# ControlID.net
KiCad netlist of a schematic drawn in EAGLE
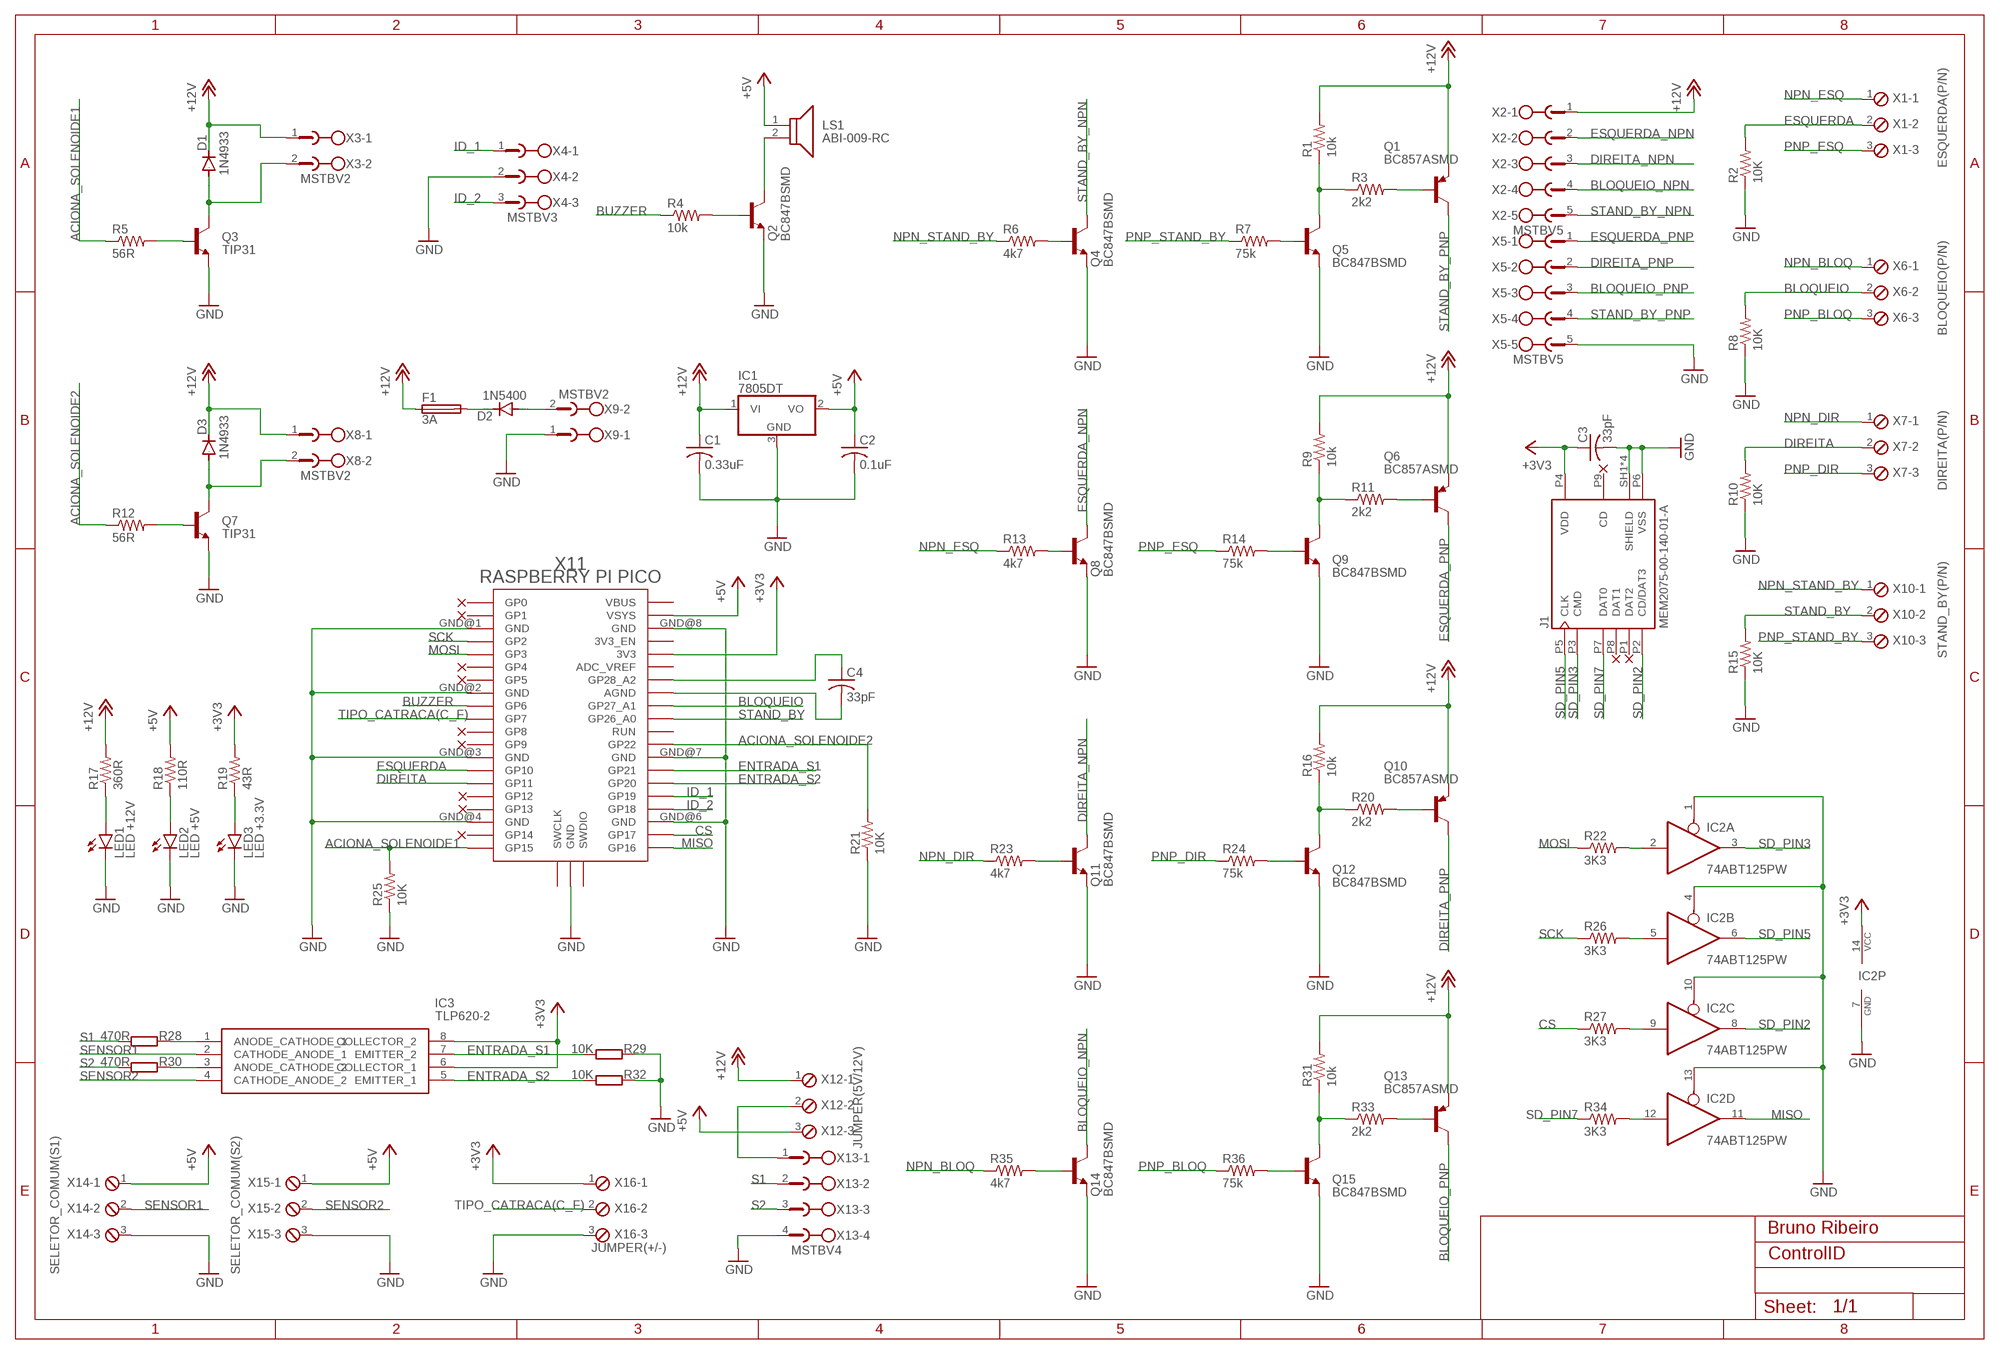
[diagram p0: schematic, sheet 1]

(export (version "E")
  (design (tool "Eeschema 10.0.6"))
  (components
    (comp (ref "C1")
      (value "0.33uF")
      (footprint "eagle-import:C0805")
      (libsource (lib "eagle-import") (part "C-USC0805"))
    )
    (comp (ref "C2")
      (value "0.1uF")
      (footprint "eagle-import:C0805")
      (libsource (lib "eagle-import") (part "C-USC0805"))
    )
    (comp (ref "C3")
      (value "33pF")
      (footprint "eagle-import:C0805")
      (libsource (lib "eagle-import") (part "C-USC0805"))
    )
    (comp (ref "C4")
      (value "33pF")
      (footprint "eagle-import:C0805")
      (libsource (lib "eagle-import") (part "C-USC0805"))
    )
    (comp (ref "D1")
      (value "1N4933")
      (footprint "eagle-import:DO41-10")
      (libsource (lib "eagle-import") (part "1N4933"))
    )
    (comp (ref "D2")
      (value "1N5400")
      (footprint "eagle-import:DO201-15")
      (libsource (lib "eagle-import") (part "1N5400"))
    )
    (comp (ref "D3")
      (value "1N4933")
      (footprint "eagle-import:DO41-10")
      (libsource (lib "eagle-import") (part "1N4933"))
    )
    (comp (ref "F1")
      (value "3A")
      (footprint "eagle-import:SH22,5A")
      (fields (field (name "MPN") "0031.7701.11"))
      (libsource (lib "eagle-import") (part "SH22,5A"))
    )
    (comp (ref "IC1")
      (value "7805DT")
      (footprint "eagle-import:TO252")
      (libsource (lib "eagle-import") (part "78DT05"))
    )
    (comp (ref "IC2")
      (value "74ABT125PW")
      (footprint "eagle-import:TSSOP14")
      (libsource (lib "eagle-import") (part "74125PWABT"))
    )
    (comp (ref "IC3")
      (value "TLP620-2")
      (footprint "eagle-import:DIP762W60P254L966H485Q8N")
      (libsource (lib "eagle-import") (part "TLP620-2"))
    )
    (comp (ref "J1")
      (value "MEM2075-00-140-01-A")
      (footprint "eagle-import:GCT_MEM2075-00-140-01-A")
      (fields (field (name "MF") "Global Connector Technology"))
      (libsource (lib "eagle-import") (part "MEM2075-00-140-01-A"))
    )
    (comp (ref "LED1")
      (value "LED +12V")
      (footprint "eagle-import:CHIP-LED0805")
      (libsource (lib "eagle-import") (part "LEDCHIP-LED0805"))
    )
    (comp (ref "LED2")
      (value "LED +5V")
      (footprint "eagle-import:CHIP-LED0805")
      (libsource (lib "eagle-import") (part "LEDCHIP-LED0805"))
    )
    (comp (ref "LED3")
      (value "LED +3.3V")
      (footprint "eagle-import:CHIP-LED0805")
      (libsource (lib "eagle-import") (part "LEDCHIP-LED0805"))
    )
    (comp (ref "LS1")
      (value "ABI-009-RC")
      (footprint "eagle-import:ABI-009-RC")
      (libsource (lib "eagle-import") (part "ABI-009-RC"))
    )
    (comp (ref "Q1")
      (value "BC857ASMD")
      (footprint "eagle-import:SOT23-BEC")
      (libsource (lib "eagle-import") (part "BC857SMDA"))
    )
    (comp (ref "Q2")
      (value "BC847BSMD")
      (footprint "eagle-import:SOT23")
      (libsource (lib "eagle-import") (part "BC847SMDB"))
    )
    (comp (ref "Q3")
      (value "TIP31")
      (footprint "eagle-import:TO254P1060X482X2222-3")
      (fields (field (name "MF") "ON Semiconductor"))
      (libsource (lib "eagle-import") (part "TIP31"))
    )
    (comp (ref "Q4")
      (value "BC847BSMD")
      (footprint "eagle-import:SOT23")
      (libsource (lib "eagle-import") (part "BC847SMDB"))
    )
    (comp (ref "Q5")
      (value "BC847BSMD")
      (footprint "eagle-import:SOT23")
      (libsource (lib "eagle-import") (part "BC847SMDB"))
    )
    (comp (ref "Q6")
      (value "BC857ASMD")
      (footprint "eagle-import:SOT23-BEC")
      (libsource (lib "eagle-import") (part "BC857SMDA"))
    )
    (comp (ref "Q7")
      (value "TIP31")
      (footprint "eagle-import:TO254P1060X482X2222-3")
      (fields (field (name "MF") "ON Semiconductor"))
      (libsource (lib "eagle-import") (part "TIP31"))
    )
    (comp (ref "Q8")
      (value "BC847BSMD")
      (footprint "eagle-import:SOT23")
      (libsource (lib "eagle-import") (part "BC847SMDB"))
    )
    (comp (ref "Q9")
      (value "BC847BSMD")
      (footprint "eagle-import:SOT23")
      (libsource (lib "eagle-import") (part "BC847SMDB"))
    )
    (comp (ref "Q10")
      (value "BC857ASMD")
      (footprint "eagle-import:SOT23-BEC")
      (libsource (lib "eagle-import") (part "BC857SMDA"))
    )
    (comp (ref "Q11")
      (value "BC847BSMD")
      (footprint "eagle-import:SOT23")
      (libsource (lib "eagle-import") (part "BC847SMDB"))
    )
    (comp (ref "Q12")
      (value "BC847BSMD")
      (footprint "eagle-import:SOT23")
      (libsource (lib "eagle-import") (part "BC847SMDB"))
    )
    (comp (ref "Q13")
      (value "BC857ASMD")
      (footprint "eagle-import:SOT23-BEC")
      (libsource (lib "eagle-import") (part "BC857SMDA"))
    )
    (comp (ref "Q14")
      (value "BC847BSMD")
      (footprint "eagle-import:SOT23")
      (libsource (lib "eagle-import") (part "BC847SMDB"))
    )
    (comp (ref "Q15")
      (value "BC847BSMD")
      (footprint "eagle-import:SOT23")
      (libsource (lib "eagle-import") (part "BC847SMDB"))
    )
    (comp (ref "R1")
      (value "10k")
      (footprint "eagle-import:R0805")
      (libsource (lib "eagle-import") (part "R-US_R0805"))
    )
    (comp (ref "R2")
      (value "10K")
      (footprint "eagle-import:R0805")
      (libsource (lib "eagle-import") (part "R-US_R0805"))
    )
    (comp (ref "R3")
      (value "2k2")
      (footprint "eagle-import:R0805")
      (libsource (lib "eagle-import") (part "R-US_R0805"))
    )
    (comp (ref "R4")
      (value "10k")
      (footprint "eagle-import:R0805")
      (libsource (lib "eagle-import") (part "R-US_R0805"))
    )
    (comp (ref "R5")
      (value "56R")
      (footprint "eagle-import:R0805")
      (libsource (lib "eagle-import") (part "R-US_R0805"))
    )
    (comp (ref "R6")
      (value "4k7")
      (footprint "eagle-import:R0805")
      (libsource (lib "eagle-import") (part "R-US_R0805"))
    )
    (comp (ref "R7")
      (value "75k")
      (footprint "eagle-import:R0805")
      (libsource (lib "eagle-import") (part "R-US_R0805"))
    )
    (comp (ref "R8")
      (value "10K")
      (footprint "eagle-import:R0805")
      (libsource (lib "eagle-import") (part "R-US_R0805"))
    )
    (comp (ref "R9")
      (value "10k")
      (footprint "eagle-import:R0805")
      (libsource (lib "eagle-import") (part "R-US_R0805"))
    )
    (comp (ref "R10")
      (value "10K")
      (footprint "eagle-import:R0805")
      (libsource (lib "eagle-import") (part "R-US_R0805"))
    )
    (comp (ref "R11")
      (value "2k2")
      (footprint "eagle-import:R0805")
      (libsource (lib "eagle-import") (part "R-US_R0805"))
    )
    (comp (ref "R12")
      (value "56R")
      (footprint "eagle-import:R0805")
      (libsource (lib "eagle-import") (part "R-US_R0805"))
    )
    (comp (ref "R13")
      (value "4k7")
      (footprint "eagle-import:R0805")
      (libsource (lib "eagle-import") (part "R-US_R0805"))
    )
    (comp (ref "R14")
      (value "75k")
      (footprint "eagle-import:R0805")
      (libsource (lib "eagle-import") (part "R-US_R0805"))
    )
    (comp (ref "R15")
      (value "10K")
      (footprint "eagle-import:R0805")
      (libsource (lib "eagle-import") (part "R-US_R0805"))
    )
    (comp (ref "R16")
      (value "10k")
      (footprint "eagle-import:R0805")
      (libsource (lib "eagle-import") (part "R-US_R0805"))
    )
    (comp (ref "R17")
      (value "360R")
      (footprint "eagle-import:R0805")
      (libsource (lib "eagle-import") (part "R-US_R0805"))
    )
    (comp (ref "R18")
      (value "110R")
      (footprint "eagle-import:R0805")
      (libsource (lib "eagle-import") (part "R-US_R0805"))
    )
    (comp (ref "R19")
      (value "43R")
      (footprint "eagle-import:R0805")
      (libsource (lib "eagle-import") (part "R-US_R0805"))
    )
    (comp (ref "R20")
      (value "2k2")
      (footprint "eagle-import:R0805")
      (libsource (lib "eagle-import") (part "R-US_R0805"))
    )
    (comp (ref "R21")
      (value "10K")
      (footprint "eagle-import:R0805")
      (libsource (lib "eagle-import") (part "R-US_R0805"))
    )
    (comp (ref "R22")
      (value "3K3")
      (footprint "eagle-import:R0805")
      (libsource (lib "eagle-import") (part "R-US_R0805"))
    )
    (comp (ref "R23")
      (value "4k7")
      (footprint "eagle-import:R0805")
      (libsource (lib "eagle-import") (part "R-US_R0805"))
    )
    (comp (ref "R24")
      (value "75k")
      (footprint "eagle-import:R0805")
      (libsource (lib "eagle-import") (part "R-US_R0805"))
    )
    (comp (ref "R25")
      (value "10K")
      (footprint "eagle-import:R0805")
      (libsource (lib "eagle-import") (part "R-US_R0805"))
    )
    (comp (ref "R26")
      (value "3K3")
      (footprint "eagle-import:R0805")
      (libsource (lib "eagle-import") (part "R-US_R0805"))
    )
    (comp (ref "R27")
      (value "3K3")
      (footprint "eagle-import:R0805")
      (libsource (lib "eagle-import") (part "R-US_R0805"))
    )
    (comp (ref "R28")
      (value "470R")
      (footprint "eagle-import:R0805")
      (libsource (lib "eagle-import") (part "R-EU_R0805"))
    )
    (comp (ref "R29")
      (value "10K")
      (footprint "eagle-import:R0805")
      (libsource (lib "eagle-import") (part "R-EU_R0805"))
    )
    (comp (ref "R30")
      (value "470R")
      (footprint "eagle-import:R0805")
      (libsource (lib "eagle-import") (part "R-EU_R0805"))
    )
    (comp (ref "R31")
      (value "10k")
      (footprint "eagle-import:R0805")
      (libsource (lib "eagle-import") (part "R-US_R0805"))
    )
    (comp (ref "R32")
      (value "10K")
      (footprint "eagle-import:R0805")
      (libsource (lib "eagle-import") (part "R-EU_R0805"))
    )
    (comp (ref "R33")
      (value "2k2")
      (footprint "eagle-import:R0805")
      (libsource (lib "eagle-import") (part "R-US_R0805"))
    )
    (comp (ref "R34")
      (value "3K3")
      (footprint "eagle-import:R0805")
      (libsource (lib "eagle-import") (part "R-US_R0805"))
    )
    (comp (ref "R35")
      (value "4k7")
      (footprint "eagle-import:R0805")
      (libsource (lib "eagle-import") (part "R-US_R0805"))
    )
    (comp (ref "R36")
      (value "75k")
      (footprint "eagle-import:R0805")
      (libsource (lib "eagle-import") (part "R-US_R0805"))
    )
    (comp (ref "X1")
      (value "ESQUERDA(P/N)")
      (footprint "eagle-import:3POL254")
      (libsource (lib "eagle-import") (part "MPT3"))
    )
    (comp (ref "X2")
      (value "MSTBV5")
      (footprint "eagle-import:MSTBV5")
      (fields (field (name "MPN") "MSTBV 2,5/5-GF-5.08"))
      (libsource (lib "eagle-import") (part "MSTBV5"))
    )
    (comp (ref "X3")
      (value "MSTBV2")
      (footprint "eagle-import:MSTBV2")
      (fields (field (name "MPN") "MSTBV 2,5/2-GF-5.08"))
      (libsource (lib "eagle-import") (part "MSTBV2"))
    )
    (comp (ref "X4")
      (value "MSTBV3")
      (footprint "eagle-import:MSTBV3")
      (fields (field (name "MPN") "MSTBV 2,5/3-GF-5.08"))
      (libsource (lib "eagle-import") (part "MSTBV3"))
    )
    (comp (ref "X5")
      (value "MSTBV5")
      (footprint "eagle-import:MSTBV5")
      (fields (field (name "MPN") "MSTBV 2,5/5-GF-5.08"))
      (libsource (lib "eagle-import") (part "MSTBV5"))
    )
    (comp (ref "X6")
      (value "BLOQUEIO(P/N)")
      (footprint "eagle-import:3POL254")
      (libsource (lib "eagle-import") (part "MPT3"))
    )
    (comp (ref "X7")
      (value "DIREITA(P/N)")
      (footprint "eagle-import:3POL254")
      (libsource (lib "eagle-import") (part "MPT3"))
    )
    (comp (ref "X8")
      (value "MSTBV2")
      (footprint "eagle-import:MSTBV2")
      (fields (field (name "MPN") "MSTBV 2,5/2-GF-5.08"))
      (libsource (lib "eagle-import") (part "MSTBV2"))
    )
    (comp (ref "X9")
      (value "MSTBV2")
      (footprint "eagle-import:MSTBV2")
      (fields (field (name "MPN") "MSTBV 2,5/2-GF-5.08"))
      (libsource (lib "eagle-import") (part "MSTBV2"))
    )
    (comp (ref "X10")
      (value "STAND_BY(P/N)")
      (footprint "eagle-import:3POL254")
      (libsource (lib "eagle-import") (part "MPT3"))
    )
    (comp (ref "X11")
      (value "RASPBERRY PI PICO")
      (footprint "eagle-import:RPI_PICO_TH")
      (libsource (lib "eagle-import") (part "RPI_PICO_IG-TH"))
    )
    (comp (ref "X12")
      (value "JUMPER(5V/12V)")
      (footprint "eagle-import:3POL254")
      (libsource (lib "eagle-import") (part "MPT3"))
    )
    (comp (ref "X13")
      (value "MSTBV4")
      (footprint "eagle-import:MSTBV4")
      (fields (field (name "MPN") "MSTBV 2,5/4-GF-5.08"))
      (libsource (lib "eagle-import") (part "MSTBV4"))
    )
    (comp (ref "X14")
      (value "SELETOR_COMUM(S1)")
      (footprint "eagle-import:3POL254")
      (libsource (lib "eagle-import") (part "MPT3"))
    )
    (comp (ref "X15")
      (value "SELETOR_COMUM(S2)")
      (footprint "eagle-import:3POL254")
      (libsource (lib "eagle-import") (part "MPT3"))
    )
    (comp (ref "X16")
      (value "JUMPER(+/-)")
      (footprint "eagle-import:3POL254")
      (libsource (lib "eagle-import") (part "MPT3"))
    )
  )
  (nets
    (net (code "1") (name "+3V3") (class "Default")
      (node (ref "C3") (pin "1") (pinfunction "1_1") (pintype "passive"))
      (node (ref "IC2") (pin "14") (pinfunction "VCC_14") (pintype "power_in"))
      (node (ref "IC3") (pin "6") (pinfunction "COLLECTOR_1_6") (pintype "bidirectional"))
      (node (ref "IC3") (pin "8") (pinfunction "COLLECTOR_2_8") (pintype "bidirectional"))
      (node (ref "J1") (pin "P4") (pinfunction "VDD_P4") (pintype "power_in"))
      (node (ref "R19") (pin "2") (pinfunction "2_2") (pintype "passive"))
      (node (ref "X11") (pin "3V3") (pinfunction "3V3_3V3") (pintype "bidirectional"))
      (node (ref "X16") (pin "1") (pinfunction "1_1") (pintype "passive"))
    )
    (net (code "2") (name "+5V") (class "Default")
      (node (ref "C2") (pin "1") (pinfunction "1_1") (pintype "passive"))
      (node (ref "IC1") (pin "2") (pinfunction "VO_2") (pintype "passive"))
      (node (ref "LS1") (pin "1") (pinfunction "1_1") (pintype "bidirectional"))
      (node (ref "R18") (pin "2") (pinfunction "2_2") (pintype "passive"))
      (node (ref "X11") (pin "VSYS") (pinfunction "VSYS_VSYS") (pintype "bidirectional"))
      (node (ref "X12") (pin "3") (pinfunction "1_3") (pintype "passive"))
      (node (ref "X14") (pin "1") (pinfunction "1_1") (pintype "passive"))
      (node (ref "X15") (pin "1") (pinfunction "1_1") (pintype "passive"))
    )
    (net (code "3") (name "+12V") (class "Default")
      (node (ref "C1") (pin "1") (pinfunction "1_1") (pintype "passive"))
      (node (ref "D1") (pin "C") (pinfunction "C_C") (pintype "passive"))
      (node (ref "D3") (pin "C") (pinfunction "C_C") (pintype "passive"))
      (node (ref "F1") (pin "1") (pinfunction "1_1") (pintype "passive"))
      (node (ref "IC1") (pin "1") (pinfunction "VI_1") (pintype "input"))
      (node (ref "Q1") (pin "E") (pinfunction "E_E") (pintype "passive"))
      (node (ref "Q10") (pin "E") (pinfunction "E_E") (pintype "passive"))
      (node (ref "Q13") (pin "E") (pinfunction "E_E") (pintype "passive"))
      (node (ref "Q6") (pin "E") (pinfunction "E_E") (pintype "passive"))
      (node (ref "R1") (pin "2") (pinfunction "2_2") (pintype "passive"))
      (node (ref "R16") (pin "2") (pinfunction "2_2") (pintype "passive"))
      (node (ref "R17") (pin "2") (pinfunction "2_2") (pintype "passive"))
      (node (ref "R31") (pin "2") (pinfunction "2_2") (pintype "passive"))
      (node (ref "R9") (pin "2") (pinfunction "2_2") (pintype "passive"))
      (node (ref "X12") (pin "1") (pinfunction "1_1") (pintype "passive"))
      (node (ref "X2") (pin "1") (pinfunction "1_1") (pintype "passive"))
      (node (ref "X3") (pin "1") (pinfunction "1_1") (pintype "passive"))
      (node (ref "X8") (pin "1") (pinfunction "1_1") (pintype "passive"))
    )
    (net (code "4") (name "/ACIONA_SOLENOIDE1") (class "Default")
      (node (ref "R25") (pin "2") (pinfunction "2_2") (pintype "passive"))
      (node (ref "R5") (pin "1") (pinfunction "1_1") (pintype "passive"))
      (node (ref "X11") (pin "GP15") (pinfunction "GP15_GP15") (pintype "bidirectional"))
    )
    (net (code "5") (name "/ACIONA_SOLENOIDE2") (class "Default")
      (node (ref "R12") (pin "1") (pinfunction "1_1") (pintype "passive"))
      (node (ref "R21") (pin "2") (pinfunction "2_2") (pintype "passive"))
      (node (ref "X11") (pin "GP22") (pinfunction "GP22_GP22") (pintype "bidirectional"))
    )
    (net (code "6") (name "/BLOQUEIO") (class "Default")
      (node (ref "R8") (pin "2") (pinfunction "2_2") (pintype "passive"))
      (node (ref "X11") (pin "GP27_A1") (pinfunction "GP27_A1_GP27_A1") (pintype "bidirectional"))
      (node (ref "X6") (pin "2") (pinfunction "1_2") (pintype "passive"))
    )
    (net (code "7") (name "/BLOQUEIO_NPN") (class "Default")
      (node (ref "Q14") (pin "3") (pinfunction "C_3") (pintype "passive"))
      (node (ref "X2") (pin "4") (pinfunction "1_4") (pintype "passive"))
    )
    (net (code "8") (name "/BLOQUEIO_PNP") (class "Default")
      (node (ref "Q13") (pin "C") (pinfunction "C_C") (pintype "passive"))
      (node (ref "X5") (pin "3") (pinfunction "1_3") (pintype "passive"))
    )
    (net (code "9") (name "/BUZZER") (class "Default")
      (node (ref "R4") (pin "1") (pinfunction "1_1") (pintype "passive"))
      (node (ref "X11") (pin "GP6") (pinfunction "GP6_GP6") (pintype "bidirectional"))
    )
    (net (code "10") (name "/CS") (class "Default")
      (node (ref "R27") (pin "1") (pinfunction "1_1") (pintype "passive"))
      (node (ref "X11") (pin "GP17") (pinfunction "GP17_GP17") (pintype "bidirectional"))
    )
    (net (code "11") (name "/DIREITA") (class "Default")
      (node (ref "R10") (pin "2") (pinfunction "2_2") (pintype "passive"))
      (node (ref "X11") (pin "GP11") (pinfunction "GP11_GP11") (pintype "bidirectional"))
      (node (ref "X7") (pin "2") (pinfunction "1_2") (pintype "passive"))
    )
    (net (code "12") (name "/DIREITA_NPN") (class "Default")
      (node (ref "Q11") (pin "3") (pinfunction "C_3") (pintype "passive"))
      (node (ref "X2") (pin "3") (pinfunction "1_3") (pintype "passive"))
    )
    (net (code "13") (name "/DIREITA_PNP") (class "Default")
      (node (ref "Q10") (pin "C") (pinfunction "C_C") (pintype "passive"))
      (node (ref "X5") (pin "2") (pinfunction "1_2") (pintype "passive"))
    )
    (net (code "14") (name "/ENTRADA_S1") (class "Default")
      (node (ref "IC3") (pin "7") (pinfunction "EMITTER_2_7") (pintype "bidirectional"))
      (node (ref "R29") (pin "2") (pinfunction "2_2") (pintype "passive"))
      (node (ref "X11") (pin "GP21") (pinfunction "GP21_GP21") (pintype "bidirectional"))
    )
    (net (code "15") (name "/ENTRADA_S2") (class "Default")
      (node (ref "IC3") (pin "5") (pinfunction "EMITTER_1_5") (pintype "bidirectional"))
      (node (ref "R32") (pin "2") (pinfunction "2_2") (pintype "passive"))
      (node (ref "X11") (pin "GP20") (pinfunction "GP20_GP20") (pintype "bidirectional"))
    )
    (net (code "16") (name "/ESQUERDA") (class "Default")
      (node (ref "R2") (pin "2") (pinfunction "2_2") (pintype "passive"))
      (node (ref "X1") (pin "2") (pinfunction "1_2") (pintype "passive"))
      (node (ref "X11") (pin "GP10") (pinfunction "GP10_GP10") (pintype "bidirectional"))
    )
    (net (code "17") (name "/ESQUERDA_NPN") (class "Default")
      (node (ref "Q8") (pin "3") (pinfunction "C_3") (pintype "passive"))
      (node (ref "X2") (pin "2") (pinfunction "1_2") (pintype "passive"))
    )
    (net (code "18") (name "/ESQUERDA_PNP") (class "Default")
      (node (ref "Q6") (pin "C") (pinfunction "C_C") (pintype "passive"))
      (node (ref "X5") (pin "1") (pinfunction "1_1") (pintype "passive"))
    )
    (net (code "19") (name "/ID_1") (class "Default")
      (node (ref "X11") (pin "GP19") (pinfunction "GP19_GP19") (pintype "bidirectional"))
      (node (ref "X4") (pin "1") (pinfunction "1_1") (pintype "passive"))
    )
    (net (code "20") (name "/ID_2") (class "Default")
      (node (ref "X11") (pin "GP18") (pinfunction "GP18_GP18") (pintype "bidirectional"))
      (node (ref "X4") (pin "3") (pinfunction "1_3") (pintype "passive"))
    )
    (net (code "21") (name "/MISO") (class "Default")
      (node (ref "IC2") (pin "11") (pinfunction "O_11") (pintype "tri_state"))
      (node (ref "X11") (pin "GP16") (pinfunction "GP16_GP16") (pintype "bidirectional"))
    )
    (net (code "22") (name "/MOSI") (class "Default")
      (node (ref "R22") (pin "1") (pinfunction "1_1") (pintype "passive"))
      (node (ref "X11") (pin "GP3") (pinfunction "GP3_GP3") (pintype "bidirectional"))
    )
    (net (code "23") (name "/NPN_BLOQ") (class "Default")
      (node (ref "R35") (pin "1") (pinfunction "1_1") (pintype "passive"))
      (node (ref "X6") (pin "1") (pinfunction "1_1") (pintype "passive"))
    )
    (net (code "24") (name "/NPN_DIR") (class "Default")
      (node (ref "R23") (pin "1") (pinfunction "1_1") (pintype "passive"))
      (node (ref "X7") (pin "1") (pinfunction "1_1") (pintype "passive"))
    )
    (net (code "25") (name "/NPN_ESQ") (class "Default")
      (node (ref "R13") (pin "1") (pinfunction "1_1") (pintype "passive"))
      (node (ref "X1") (pin "1") (pinfunction "1_1") (pintype "passive"))
    )
    (net (code "26") (name "/NPN_STAND_BY") (class "Default")
      (node (ref "R6") (pin "1") (pinfunction "1_1") (pintype "passive"))
      (node (ref "X10") (pin "1") (pinfunction "1_1") (pintype "passive"))
    )
    (net (code "27") (name "/PNP_BLOQ") (class "Default")
      (node (ref "R36") (pin "1") (pinfunction "1_1") (pintype "passive"))
      (node (ref "X6") (pin "3") (pinfunction "1_3") (pintype "passive"))
    )
    (net (code "28") (name "/PNP_DIR") (class "Default")
      (node (ref "R24") (pin "1") (pinfunction "1_1") (pintype "passive"))
      (node (ref "X7") (pin "3") (pinfunction "1_3") (pintype "passive"))
    )
    (net (code "29") (name "/PNP_ESQ") (class "Default")
      (node (ref "R14") (pin "1") (pinfunction "1_1") (pintype "passive"))
      (node (ref "X1") (pin "3") (pinfunction "1_3") (pintype "passive"))
    )
    (net (code "30") (name "/PNP_STAND_BY") (class "Default")
      (node (ref "R7") (pin "1") (pinfunction "1_1") (pintype "passive"))
      (node (ref "X10") (pin "3") (pinfunction "1_3") (pintype "passive"))
    )
    (net (code "31") (name "/S1") (class "Default")
      (node (ref "R28") (pin "2") (pinfunction "2_2") (pintype "passive"))
      (node (ref "X13") (pin "2") (pinfunction "1_2") (pintype "passive"))
    )
    (net (code "32") (name "/S2") (class "Default")
      (node (ref "R30") (pin "2") (pinfunction "2_2") (pintype "passive"))
      (node (ref "X13") (pin "3") (pinfunction "1_3") (pintype "passive"))
    )
    (net (code "33") (name "/SCK") (class "Default")
      (node (ref "R26") (pin "1") (pinfunction "1_1") (pintype "passive"))
      (node (ref "X11") (pin "GP2") (pinfunction "GP2_GP2") (pintype "bidirectional"))
    )
    (net (code "34") (name "/SD_PIN2") (class "Default")
      (node (ref "IC2") (pin "8") (pinfunction "O_8") (pintype "tri_state"))
      (node (ref "J1") (pin "P2") (pinfunction "CD/DAT3_P2") (pintype "bidirectional"))
    )
    (net (code "35") (name "/SD_PIN3") (class "Default")
      (node (ref "IC2") (pin "3") (pinfunction "O_3") (pintype "tri_state"))
      (node (ref "J1") (pin "P3") (pinfunction "CMD_P3") (pintype "bidirectional"))
    )
    (net (code "36") (name "/SD_PIN5") (class "Default")
      (node (ref "IC2") (pin "6") (pinfunction "O_6") (pintype "tri_state"))
      (node (ref "J1") (pin "P5") (pinfunction "CLK_P5") (pintype "bidirectional"))
    )
    (net (code "37") (name "/SD_PIN7") (class "Default")
      (node (ref "J1") (pin "P7") (pinfunction "DAT0_P7") (pintype "bidirectional"))
      (node (ref "R34") (pin "1") (pinfunction "1_1") (pintype "passive"))
    )
    (net (code "38") (name "/SENSOR1") (class "Default")
      (node (ref "IC3") (pin "2") (pinfunction "CATHODE_ANODE_1_2") (pintype "bidirectional"))
      (node (ref "X14") (pin "2") (pinfunction "1_2") (pintype "passive"))
    )
    (net (code "39") (name "/SENSOR2") (class "Default")
      (node (ref "IC3") (pin "4") (pinfunction "CATHODE_ANODE_2_4") (pintype "bidirectional"))
      (node (ref "X15") (pin "2") (pinfunction "1_2") (pintype "passive"))
    )
    (net (code "40") (name "/STAND_BY") (class "Default")
      (node (ref "R15") (pin "2") (pinfunction "2_2") (pintype "passive"))
      (node (ref "X10") (pin "2") (pinfunction "1_2") (pintype "passive"))
      (node (ref "X11") (pin "GP26_A0") (pinfunction "GP26_A0_GP26_A0") (pintype "bidirectional"))
    )
    (net (code "41") (name "/STAND_BY_NPN") (class "Default")
      (node (ref "Q4") (pin "3") (pinfunction "C_3") (pintype "passive"))
      (node (ref "X2") (pin "5") (pinfunction "1_5") (pintype "passive"))
    )
    (net (code "42") (name "/STAND_BY_PNP") (class "Default")
      (node (ref "Q1") (pin "C") (pinfunction "C_C") (pintype "passive"))
      (node (ref "X5") (pin "4") (pinfunction "1_4") (pintype "passive"))
    )
    (net (code "43") (name "/TIPO_CATRACA(C_F)") (class "Default")
      (node (ref "X11") (pin "GP7") (pinfunction "GP7_GP7") (pintype "bidirectional"))
      (node (ref "X16") (pin "2") (pinfunction "1_2") (pintype "passive"))
    )
    (net (code "44") (name "GND") (class "Default")
      (node (ref "C1") (pin "2") (pinfunction "2_2") (pintype "passive"))
      (node (ref "C2") (pin "2") (pinfunction "2_2") (pintype "passive"))
      (node (ref "C3") (pin "2") (pinfunction "2_2") (pintype "passive"))
      (node (ref "IC1") (pin "3") (pinfunction "GND_3") (pintype "passive"))
      (node (ref "IC2") (pin "1") (pinfunction "OE_1") (pintype "input"))
      (node (ref "IC2") (pin "10") (pinfunction "OE_10") (pintype "input"))
      (node (ref "IC2") (pin "13") (pinfunction "OE_13") (pintype "input"))
      (node (ref "IC2") (pin "4") (pinfunction "OE_4") (pintype "input"))
      (node (ref "IC2") (pin "7") (pinfunction "GND_7") (pintype "power_in"))
      (node (ref "J1") (pin "P6") (pinfunction "VSS_P6") (pintype "power_in"))
      (node (ref "J1") (pin "SH1") (pinfunction "SHIELD_SH1") (pintype "power_in"))
      (node (ref "J1") (pin "SH2") (pinfunction "SHIELD_SH2") (pintype "power_in"))
      (node (ref "J1") (pin "SH3") (pinfunction "SHIELD_SH3") (pintype "power_in"))
      (node (ref "J1") (pin "SH4") (pinfunction "SHIELD_SH4") (pintype "power_in"))
      (node (ref "LED1") (pin "C") (pinfunction "C_C") (pintype "passive"))
      (node (ref "LED2") (pin "C") (pinfunction "C_C") (pintype "passive"))
      (node (ref "LED3") (pin "C") (pinfunction "C_C") (pintype "passive"))
      (node (ref "Q11") (pin "2") (pinfunction "E_2") (pintype "passive"))
      (node (ref "Q12") (pin "2") (pinfunction "E_2") (pintype "passive"))
      (node (ref "Q14") (pin "2") (pinfunction "E_2") (pintype "passive"))
      (node (ref "Q15") (pin "2") (pinfunction "E_2") (pintype "passive"))
      (node (ref "Q2") (pin "2") (pinfunction "E_2") (pintype "passive"))
      (node (ref "Q3") (pin "3") (pinfunction "E_3") (pintype "passive"))
      (node (ref "Q4") (pin "2") (pinfunction "E_2") (pintype "passive"))
      (node (ref "Q5") (pin "2") (pinfunction "E_2") (pintype "passive"))
      (node (ref "Q7") (pin "3") (pinfunction "E_3") (pintype "passive"))
      (node (ref "Q8") (pin "2") (pinfunction "E_2") (pintype "passive"))
      (node (ref "Q9") (pin "2") (pinfunction "E_2") (pintype "passive"))
      (node (ref "R10") (pin "1") (pinfunction "1_1") (pintype "passive"))
      (node (ref "R15") (pin "1") (pinfunction "1_1") (pintype "passive"))
      (node (ref "R2") (pin "1") (pinfunction "1_1") (pintype "passive"))
      (node (ref "R21") (pin "1") (pinfunction "1_1") (pintype "passive"))
      (node (ref "R25") (pin "1") (pinfunction "1_1") (pintype "passive"))
      (node (ref "R29") (pin "1") (pinfunction "1_1") (pintype "passive"))
      (node (ref "R32") (pin "1") (pinfunction "1_1") (pintype "passive"))
      (node (ref "R8") (pin "1") (pinfunction "1_1") (pintype "passive"))
      (node (ref "X11") (pin "GND@1") (pinfunction "GND_GND@1") (pintype "bidirectional"))
      (node (ref "X11") (pin "GND@2") (pinfunction "GND_GND@2") (pintype "bidirectional"))
      (node (ref "X11") (pin "GND@3") (pinfunction "GND_GND@3") (pintype "bidirectional"))
      (node (ref "X11") (pin "GND@4") (pinfunction "GND_GND@4") (pintype "bidirectional"))
      (node (ref "X11") (pin "GND@5") (pinfunction "GND_GND@5") (pintype "bidirectional"))
      (node (ref "X11") (pin "GND@6") (pinfunction "GND_GND@6") (pintype "bidirectional"))
      (node (ref "X11") (pin "GND@7") (pinfunction "GND_GND@7") (pintype "bidirectional"))
      (node (ref "X11") (pin "GND@8") (pinfunction "GND_GND@8") (pintype "bidirectional"))
      (node (ref "X13") (pin "4") (pinfunction "1_4") (pintype "passive"))
      (node (ref "X14") (pin "3") (pinfunction "1_3") (pintype "passive"))
      (node (ref "X15") (pin "3") (pinfunction "1_3") (pintype "passive"))
      (node (ref "X16") (pin "3") (pinfunction "1_3") (pintype "passive"))
      (node (ref "X4") (pin "2") (pinfunction "1_2") (pintype "passive"))
      (node (ref "X5") (pin "5") (pinfunction "1_5") (pintype "passive"))
      (node (ref "X9") (pin "1") (pinfunction "1_1") (pintype "passive"))
    )
    (net (code "45") (name "Net-(C4-Pad1)") (class "Default")
      (node (ref "C4") (pin "1") (pinfunction "1_1") (pintype "passive"))
      (node (ref "X11") (pin "GP28_A2") (pinfunction "GP28_A2_GP28_A2") (pintype "bidirectional"))
    )
    (net (code "46") (name "Net-(C4-Pad2)") (class "Default")
      (node (ref "C4") (pin "2") (pinfunction "2_2") (pintype "passive"))
      (node (ref "X11") (pin "AGND") (pinfunction "AGND_AGND") (pintype "bidirectional"))
    )
    (net (code "47") (name "Net-(D2-PadC)") (class "Default")
      (node (ref "D2") (pin "C") (pinfunction "C_C") (pintype "passive"))
      (node (ref "F1") (pin "2") (pinfunction "2_2") (pintype "passive"))
    )
    (net (code "48") (name "Net-(IC2A-I)") (class "Default")
      (node (ref "IC2") (pin "2") (pinfunction "I_2") (pintype "input"))
      (node (ref "R22") (pin "2") (pinfunction "2_2") (pintype "passive"))
    )
    (net (code "49") (name "Net-(IC2B-I)") (class "Default")
      (node (ref "IC2") (pin "5") (pinfunction "I_5") (pintype "input"))
      (node (ref "R26") (pin "2") (pinfunction "2_2") (pintype "passive"))
    )
    (net (code "50") (name "Net-(IC2C-I)") (class "Default")
      (node (ref "IC2") (pin "9") (pinfunction "I_9") (pintype "input"))
      (node (ref "R27") (pin "2") (pinfunction "2_2") (pintype "passive"))
    )
    (net (code "51") (name "Net-(IC2D-I)") (class "Default")
      (node (ref "IC2") (pin "12") (pinfunction "I_12") (pintype "input"))
      (node (ref "R34") (pin "2") (pinfunction "2_2") (pintype "passive"))
    )
    (net (code "52") (name "Net-(IC3-ANODE_CATHODE_1)") (class "Default")
      (node (ref "IC3") (pin "1") (pinfunction "ANODE_CATHODE_1_1") (pintype "bidirectional"))
      (node (ref "R28") (pin "1") (pinfunction "1_1") (pintype "passive"))
    )
    (net (code "53") (name "Net-(IC3-ANODE_CATHODE_2)") (class "Default")
      (node (ref "IC3") (pin "3") (pinfunction "ANODE_CATHODE_2_3") (pintype "bidirectional"))
      (node (ref "R30") (pin "1") (pinfunction "1_1") (pintype "passive"))
    )
    (net (code "54") (name "Net-(LED1-PadA)") (class "Default")
      (node (ref "LED1") (pin "A") (pinfunction "A_A") (pintype "passive"))
      (node (ref "R17") (pin "1") (pinfunction "1_1") (pintype "passive"))
    )
    (net (code "55") (name "Net-(LED2-PadA)") (class "Default")
      (node (ref "LED2") (pin "A") (pinfunction "A_A") (pintype "passive"))
      (node (ref "R18") (pin "1") (pinfunction "1_1") (pintype "passive"))
    )
    (net (code "56") (name "Net-(LED3-PadA)") (class "Default")
      (node (ref "LED3") (pin "A") (pinfunction "A_A") (pintype "passive"))
      (node (ref "R19") (pin "1") (pinfunction "1_1") (pintype "passive"))
    )
    (net (code "57") (name "Net-(Q1-PadB)") (class "Default")
      (node (ref "Q1") (pin "B") (pinfunction "B_B") (pintype "passive"))
      (node (ref "R3") (pin "2") (pinfunction "2_2") (pintype "passive"))
    )
    (net (code "58") (name "Net-(Q2-B)") (class "Default")
      (node (ref "Q2") (pin "1") (pinfunction "B_1") (pintype "passive"))
      (node (ref "R4") (pin "2") (pinfunction "2_2") (pintype "passive"))
    )
    (net (code "59") (name "Net-(Q2-C)") (class "Default")
      (node (ref "LS1") (pin "2") (pinfunction "2_2") (pintype "bidirectional"))
      (node (ref "Q2") (pin "3") (pinfunction "C_3") (pintype "passive"))
    )
    (net (code "60") (name "Net-(Q3-B)") (class "Default")
      (node (ref "Q3") (pin "1") (pinfunction "B_1") (pintype "passive"))
      (node (ref "R5") (pin "2") (pinfunction "2_2") (pintype "passive"))
    )
    (net (code "61") (name "Net-(Q3-C)") (class "Default")
      (node (ref "D1") (pin "A") (pinfunction "A_A") (pintype "passive"))
      (node (ref "Q3") (pin "2") (pinfunction "C_2") (pintype "passive"))
      (node (ref "X3") (pin "2") (pinfunction "1_2") (pintype "passive"))
    )
    (net (code "62") (name "Net-(Q4-B)") (class "Default")
      (node (ref "Q4") (pin "1") (pinfunction "B_1") (pintype "passive"))
      (node (ref "R6") (pin "2") (pinfunction "2_2") (pintype "passive"))
    )
    (net (code "63") (name "Net-(Q5-B)") (class "Default")
      (node (ref "Q5") (pin "1") (pinfunction "B_1") (pintype "passive"))
      (node (ref "R7") (pin "2") (pinfunction "2_2") (pintype "passive"))
    )
    (net (code "64") (name "Net-(Q5-C)") (class "Default")
      (node (ref "Q5") (pin "3") (pinfunction "C_3") (pintype "passive"))
      (node (ref "R1") (pin "1") (pinfunction "1_1") (pintype "passive"))
      (node (ref "R3") (pin "1") (pinfunction "1_1") (pintype "passive"))
    )
    (net (code "65") (name "Net-(Q6-PadB)") (class "Default")
      (node (ref "Q6") (pin "B") (pinfunction "B_B") (pintype "passive"))
      (node (ref "R11") (pin "2") (pinfunction "2_2") (pintype "passive"))
    )
    (net (code "66") (name "Net-(Q7-B)") (class "Default")
      (node (ref "Q7") (pin "1") (pinfunction "B_1") (pintype "passive"))
      (node (ref "R12") (pin "2") (pinfunction "2_2") (pintype "passive"))
    )
    (net (code "67") (name "Net-(Q7-C)") (class "Default")
      (node (ref "D3") (pin "A") (pinfunction "A_A") (pintype "passive"))
      (node (ref "Q7") (pin "2") (pinfunction "C_2") (pintype "passive"))
      (node (ref "X8") (pin "2") (pinfunction "1_2") (pintype "passive"))
    )
    (net (code "68") (name "Net-(Q8-B)") (class "Default")
      (node (ref "Q8") (pin "1") (pinfunction "B_1") (pintype "passive"))
      (node (ref "R13") (pin "2") (pinfunction "2_2") (pintype "passive"))
    )
    (net (code "69") (name "Net-(Q9-B)") (class "Default")
      (node (ref "Q9") (pin "1") (pinfunction "B_1") (pintype "passive"))
      (node (ref "R14") (pin "2") (pinfunction "2_2") (pintype "passive"))
    )
    (net (code "70") (name "Net-(Q9-C)") (class "Default")
      (node (ref "Q9") (pin "3") (pinfunction "C_3") (pintype "passive"))
      (node (ref "R11") (pin "1") (pinfunction "1_1") (pintype "passive"))
      (node (ref "R9") (pin "1") (pinfunction "1_1") (pintype "passive"))
    )
    (net (code "71") (name "Net-(Q10-PadB)") (class "Default")
      (node (ref "Q10") (pin "B") (pinfunction "B_B") (pintype "passive"))
      (node (ref "R20") (pin "2") (pinfunction "2_2") (pintype "passive"))
    )
    (net (code "72") (name "Net-(Q11-B)") (class "Default")
      (node (ref "Q11") (pin "1") (pinfunction "B_1") (pintype "passive"))
      (node (ref "R23") (pin "2") (pinfunction "2_2") (pintype "passive"))
    )
    (net (code "73") (name "Net-(Q12-B)") (class "Default")
      (node (ref "Q12") (pin "1") (pinfunction "B_1") (pintype "passive"))
      (node (ref "R24") (pin "2") (pinfunction "2_2") (pintype "passive"))
    )
    (net (code "74") (name "Net-(Q12-C)") (class "Default")
      (node (ref "Q12") (pin "3") (pinfunction "C_3") (pintype "passive"))
      (node (ref "R16") (pin "1") (pinfunction "1_1") (pintype "passive"))
      (node (ref "R20") (pin "1") (pinfunction "1_1") (pintype "passive"))
    )
    (net (code "75") (name "Net-(Q13-PadB)") (class "Default")
      (node (ref "Q13") (pin "B") (pinfunction "B_B") (pintype "passive"))
      (node (ref "R33") (pin "2") (pinfunction "2_2") (pintype "passive"))
    )
    (net (code "76") (name "Net-(Q14-B)") (class "Default")
      (node (ref "Q14") (pin "1") (pinfunction "B_1") (pintype "passive"))
      (node (ref "R35") (pin "2") (pinfunction "2_2") (pintype "passive"))
    )
    (net (code "77") (name "Net-(Q15-B)") (class "Default")
      (node (ref "Q15") (pin "1") (pinfunction "B_1") (pintype "passive"))
      (node (ref "R36") (pin "2") (pinfunction "2_2") (pintype "passive"))
    )
    (net (code "78") (name "Net-(Q15-C)") (class "Default")
      (node (ref "Q15") (pin "3") (pinfunction "C_3") (pintype "passive"))
      (node (ref "R31") (pin "1") (pinfunction "1_1") (pintype "passive"))
      (node (ref "R33") (pin "1") (pinfunction "1_1") (pintype "passive"))
    )
    (net (code "79") (name "Net-(X9B-1)") (class "Default")
      (node (ref "D2") (pin "A") (pinfunction "A_A") (pintype "passive"))
      (node (ref "X9") (pin "2") (pinfunction "1_2") (pintype "passive"))
    )
    (net (code "80") (name "Net-(X12B-1)") (class "Default")
      (node (ref "X12") (pin "2") (pinfunction "1_2") (pintype "passive"))
      (node (ref "X13") (pin "1") (pinfunction "1_1") (pintype "passive"))
    )
    (net (code "81") (name "unconnected-(J1-CD-PadP9)") (class "Default")
      (node (ref "J1") (pin "P9") (pinfunction "CD_P9") (pintype "passive"))
    )
    (net (code "82") (name "unconnected-(J1-DAT1-PadP8)") (class "Default")
      (node (ref "J1") (pin "P8") (pinfunction "DAT1_P8") (pintype "bidirectional"))
    )
    (net (code "83") (name "unconnected-(J1-DAT2-PadP1)") (class "Default")
      (node (ref "J1") (pin "P1") (pinfunction "DAT2_P1") (pintype "bidirectional"))
    )
    (net (code "84") (name "unconnected-(X11-Pad3V3_EN)") (class "Default")
      (node (ref "X11") (pin "3V3_EN") (pinfunction "3V3_EN_3V3_EN") (pintype "bidirectional"))
    )
    (net (code "85") (name "unconnected-(X11-PadADC_VREF)") (class "Default")
      (node (ref "X11") (pin "ADC_VREF") (pinfunction "ADC_VREF_ADC_VREF") (pintype "bidirectional"))
    )
    (net (code "86") (name "unconnected-(X11-PadGP0)") (class "Default")
      (node (ref "X11") (pin "GP0") (pinfunction "GP0_GP0") (pintype "bidirectional"))
    )
    (net (code "87") (name "unconnected-(X11-PadGP1)") (class "Default")
      (node (ref "X11") (pin "GP1") (pinfunction "GP1_GP1") (pintype "bidirectional"))
    )
    (net (code "88") (name "unconnected-(X11-PadGP4)") (class "Default")
      (node (ref "X11") (pin "GP4") (pinfunction "GP4_GP4") (pintype "bidirectional"))
    )
    (net (code "89") (name "unconnected-(X11-PadGP5)") (class "Default")
      (node (ref "X11") (pin "GP5") (pinfunction "GP5_GP5") (pintype "bidirectional"))
    )
    (net (code "90") (name "unconnected-(X11-PadGP8)") (class "Default")
      (node (ref "X11") (pin "GP8") (pinfunction "GP8_GP8") (pintype "bidirectional"))
    )
    (net (code "91") (name "unconnected-(X11-PadGP9)") (class "Default")
      (node (ref "X11") (pin "GP9") (pinfunction "GP9_GP9") (pintype "bidirectional"))
    )
    (net (code "92") (name "unconnected-(X11-PadGP12)") (class "Default")
      (node (ref "X11") (pin "GP12") (pinfunction "GP12_GP12") (pintype "bidirectional"))
    )
    (net (code "93") (name "unconnected-(X11-PadGP13)") (class "Default")
      (node (ref "X11") (pin "GP13") (pinfunction "GP13_GP13") (pintype "bidirectional"))
    )
    (net (code "94") (name "unconnected-(X11-PadGP14)") (class "Default")
      (node (ref "X11") (pin "GP14") (pinfunction "GP14_GP14") (pintype "bidirectional"))
    )
    (net (code "95") (name "unconnected-(X11-PadRUN)") (class "Default")
      (node (ref "X11") (pin "RUN") (pinfunction "RUN_RUN") (pintype "bidirectional"))
    )
    (net (code "96") (name "unconnected-(X11-PadSWCLK)") (class "Default")
      (node (ref "X11") (pin "SWCLK") (pinfunction "SWCLK_SWCLK") (pintype "bidirectional"))
    )
    (net (code "97") (name "unconnected-(X11-PadSWDIO)") (class "Default")
      (node (ref "X11") (pin "SWDIO") (pinfunction "SWDIO_SWDIO") (pintype "bidirectional"))
    )
    (net (code "98") (name "unconnected-(X11-PadVBUS)") (class "Default")
      (node (ref "X11") (pin "VBUS") (pinfunction "VBUS_VBUS") (pintype "bidirectional"))
    )
  )
)
